# Robottino_V2.net
KiCad netlist of a schematic drawn in EAGLE
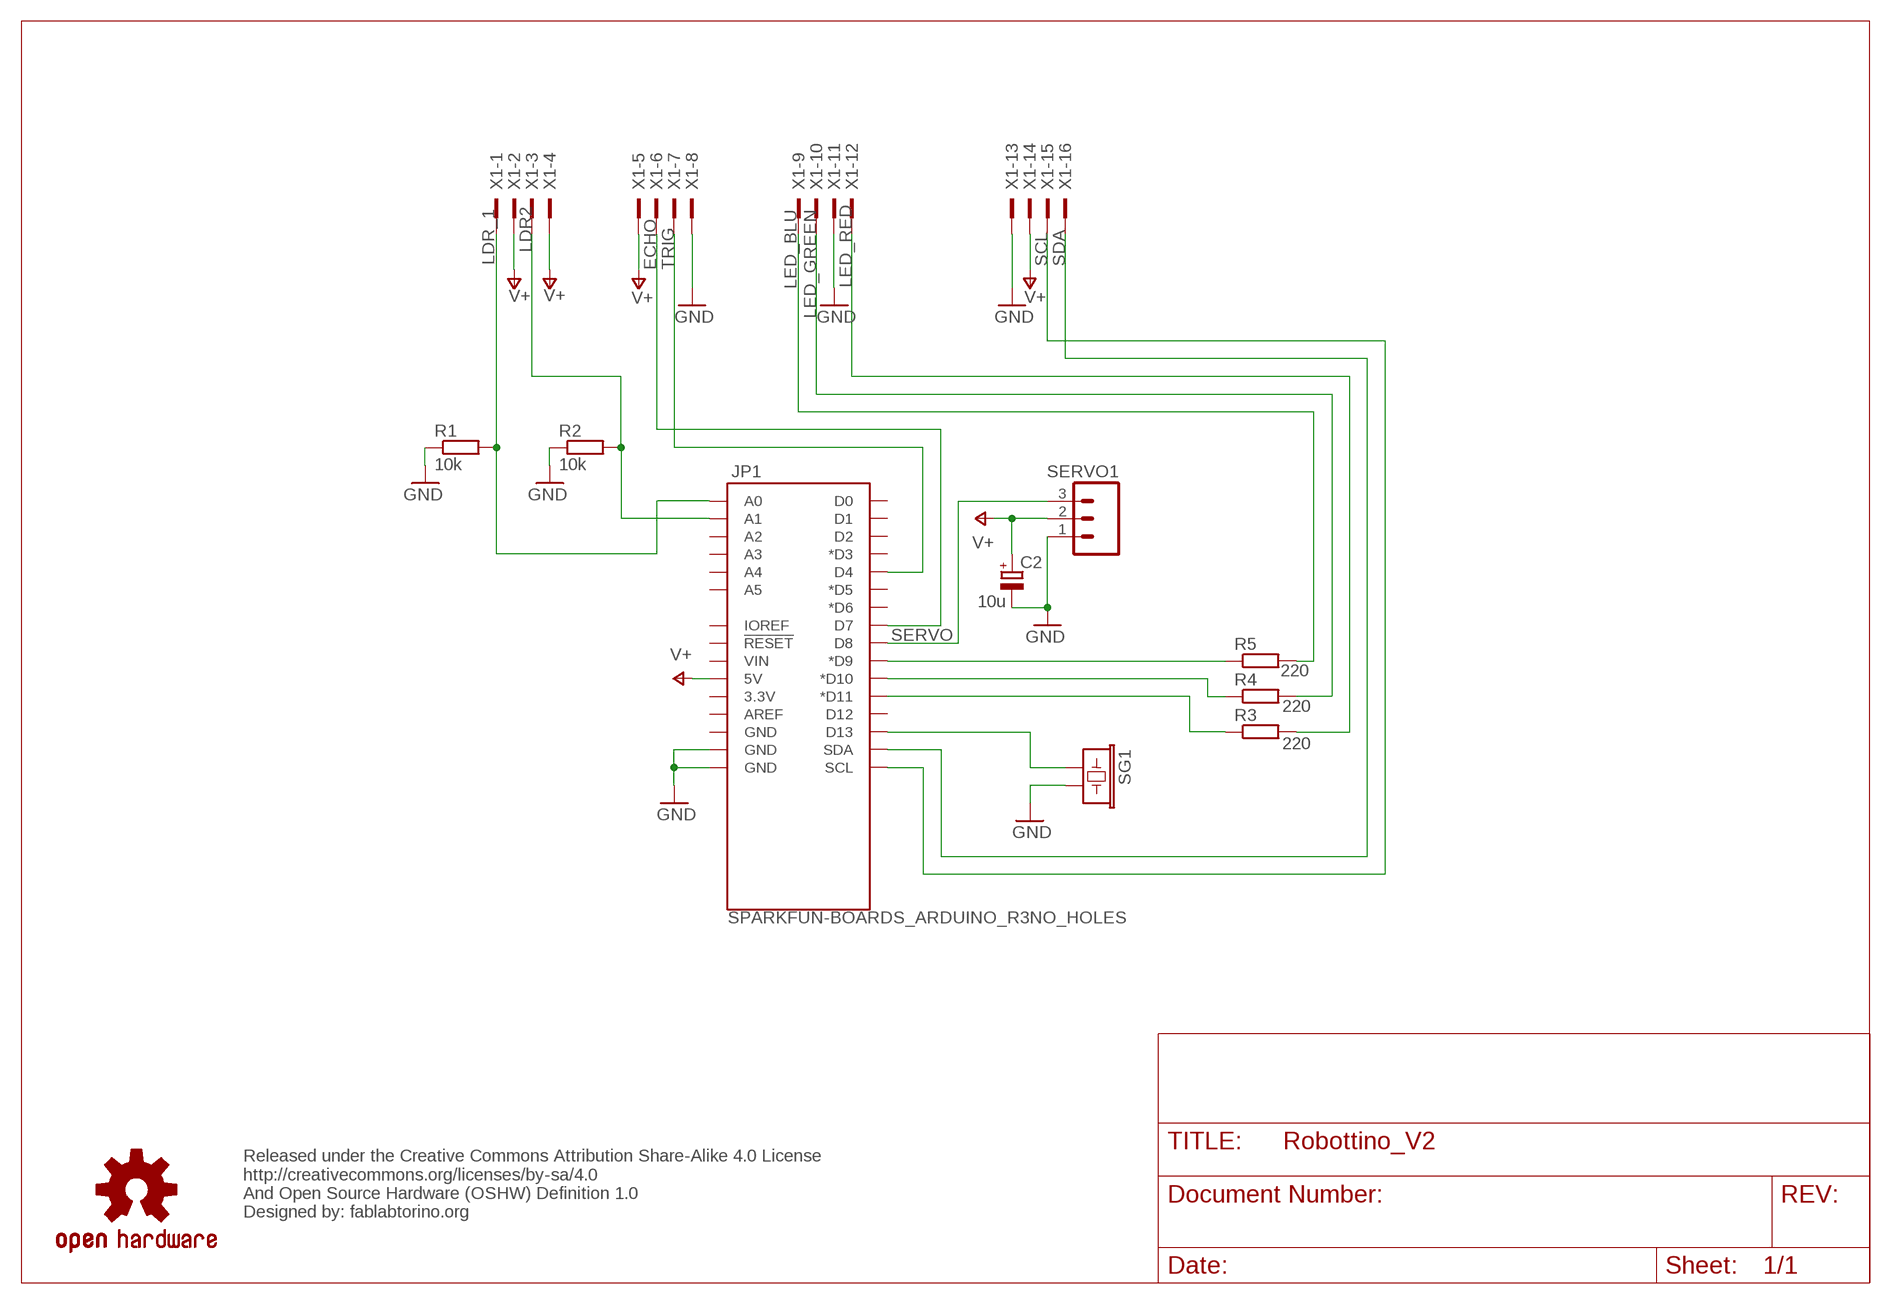
[diagram p0: schematic, sheet 1]

(export (version "E")
  (design (tool "Eeschema 10.0.6"))
  (components
    (comp (ref "C2")
      (value "10u")
      (footprint "eagle-import:E2,5-6")
      (libsource (lib "eagle-import") (part "CPOL-EUE2.5-6"))
    )
    (comp (ref "JP1")
      (value "SPARKFUN-BOARDS_ARDUINO_R3NO_HOLES")
      (footprint "eagle-import:SPARKFUN-BOARDS_ARDUINO_R3_NO_HOLES")
      (libsource (lib "eagle-import") (part "SPARKFUN-BOARDS_ARDUINO_R3NO_HOLES"))
    )
    (comp (ref "LOGO1")
      (value "OSHW-LOGOS")
      (footprint "eagle-import:OSHW-LOGO-S")
      (libsource (lib "eagle-import") (part "OSHW-LOGOS"))
    )
    (comp (ref "R1")
      (value "10k")
      (footprint "eagle-import:0309_10")
      (libsource (lib "eagle-import") (part "R-EU_0309/10"))
    )
    (comp (ref "R2")
      (value "10k")
      (footprint "eagle-import:0309_10")
      (libsource (lib "eagle-import") (part "R-EU_0309/10"))
    )
    (comp (ref "R3")
      (value "220")
      (footprint "eagle-import:0309_10")
      (libsource (lib "eagle-import") (part "R-EU_0309/10"))
    )
    (comp (ref "R4")
      (value "220")
      (footprint "eagle-import:0309_10")
      (libsource (lib "eagle-import") (part "R-EU_0309/10"))
    )
    (comp (ref "R5")
      (value "220")
      (footprint "eagle-import:0309_10")
      (libsource (lib "eagle-import") (part "R-EU_0309/10"))
    )
    (comp (ref "SERVO1")
      (value "M03POLAR")
      (footprint "eagle-import:MOLEX-1X3")
      (libsource (lib "eagle-import") (part "M03POLAR"))
    )
    (comp (ref "SG1")
      (value "SPARKFUN-ELECTROMECHANICAL_BUZZERPTH-NS-KIT")
      (footprint "eagle-import:SPARKFUN-ELECTROMECHANICAL_BUZZER-12MM-NS-KIT")
      (libsource (lib "eagle-import") (part "SPARKFUN-ELECTROMECHANICAL_BUZZERPTH-NS-KIT"))
    )
    (comp (ref "X1")
      (value "2516-")
      (footprint "eagle-import:PAK100_2500-16")
      (libsource (lib "eagle-import") (part "2516-"))
    )
  )
  (nets
    (net (code "1") (name "/ECHO") (class "Default")
      (node (ref "JP1") (pin "D4") (pinfunction "D4_D4") (pintype "bidirectional"))
      (node (ref "X1") (pin "7") (pinfunction "KL_7") (pintype "passive"))
    )
    (net (code "2") (name "/LDR2") (class "Default")
      (node (ref "JP1") (pin "A1") (pinfunction "A1_A1") (pintype "bidirectional"))
      (node (ref "R2") (pin "2") (pinfunction "2_2") (pintype "passive"))
      (node (ref "X1") (pin "3") (pinfunction "KL_3") (pintype "passive"))
    )
    (net (code "3") (name "/LDR_1") (class "Default")
      (node (ref "JP1") (pin "A0") (pinfunction "A0_A0") (pintype "bidirectional"))
      (node (ref "R1") (pin "2") (pinfunction "2_2") (pintype "passive"))
      (node (ref "X1") (pin "1") (pinfunction "KL_1") (pintype "passive"))
    )
    (net (code "4") (name "/LED_BLU") (class "Default")
      (node (ref "R5") (pin "2") (pinfunction "2_2") (pintype "passive"))
      (node (ref "X1") (pin "9") (pinfunction "KL_9") (pintype "passive"))
    )
    (net (code "5") (name "/LED_GREEN") (class "Default")
      (node (ref "R4") (pin "2") (pinfunction "2_2") (pintype "passive"))
      (node (ref "X1") (pin "10") (pinfunction "KL_10") (pintype "passive"))
    )
    (net (code "6") (name "/LED_RED") (class "Default")
      (node (ref "R3") (pin "2") (pinfunction "2_2") (pintype "passive"))
      (node (ref "X1") (pin "12") (pinfunction "KL_12") (pintype "passive"))
    )
    (net (code "7") (name "/SCL") (class "Default")
      (node (ref "JP1") (pin "SCL") (pinfunction "SCL_SCL") (pintype "bidirectional"))
      (node (ref "X1") (pin "15") (pinfunction "KL_15") (pintype "passive"))
    )
    (net (code "8") (name "/SDA") (class "Default")
      (node (ref "JP1") (pin "SDA") (pinfunction "SDA_SDA") (pintype "bidirectional"))
      (node (ref "X1") (pin "16") (pinfunction "KL_16") (pintype "passive"))
    )
    (net (code "9") (name "/SERVO") (class "Default")
      (node (ref "JP1") (pin "D8") (pinfunction "D8_D8") (pintype "bidirectional"))
      (node (ref "SERVO1") (pin "3") (pinfunction "3_3") (pintype "passive"))
    )
    (net (code "10") (name "/TRIG") (class "Default")
      (node (ref "JP1") (pin "D7") (pinfunction "D7_D7") (pintype "bidirectional"))
      (node (ref "X1") (pin "6") (pinfunction "KL_6") (pintype "passive"))
    )
    (net (code "11") (name "GND") (class "Default")
      (node (ref "C2") (pin "-") (pinfunction "-_-") (pintype "passive"))
      (node (ref "JP1") (pin "GND@1") (pinfunction "GND_GND@1") (pintype "bidirectional"))
      (node (ref "JP1") (pin "GND@2") (pinfunction "GND_GND@2") (pintype "bidirectional"))
      (node (ref "R1") (pin "1") (pinfunction "1_1") (pintype "passive"))
      (node (ref "R2") (pin "1") (pinfunction "1_1") (pintype "passive"))
      (node (ref "SERVO1") (pin "1") (pinfunction "1_1") (pintype "passive"))
      (node (ref "SG1") (pin "-") (pinfunction "2_-") (pintype "passive"))
      (node (ref "X1") (pin "11") (pinfunction "KL_11") (pintype "passive"))
      (node (ref "X1") (pin "13") (pinfunction "KL_13") (pintype "passive"))
      (node (ref "X1") (pin "8") (pinfunction "KL_8") (pintype "passive"))
    )
    (net (code "12") (name "Net-(JP1-*D9)") (class "Default")
      (node (ref "JP1") (pin "D9") (pinfunction "*D9_D9") (pintype "bidirectional"))
      (node (ref "R5") (pin "1") (pinfunction "1_1") (pintype "passive"))
    )
    (net (code "13") (name "Net-(JP1-*D10)") (class "Default")
      (node (ref "JP1") (pin "D10") (pinfunction "*D10_D10") (pintype "bidirectional"))
      (node (ref "R4") (pin "1") (pinfunction "1_1") (pintype "passive"))
    )
    (net (code "14") (name "Net-(JP1-*D11)") (class "Default")
      (node (ref "JP1") (pin "D11") (pinfunction "*D11_D11") (pintype "bidirectional"))
      (node (ref "R3") (pin "1") (pinfunction "1_1") (pintype "passive"))
    )
    (net (code "15") (name "Net-(SG1-1)") (class "Default")
      (node (ref "JP1") (pin "D13") (pinfunction "D13_D13") (pintype "bidirectional"))
      (node (ref "SG1") (pin "+") (pinfunction "1_+") (pintype "passive"))
    )
    (net (code "16") (name "V+") (class "Default")
      (node (ref "C2") (pin "+") (pinfunction "+_+") (pintype "passive"))
      (node (ref "JP1") (pin "5V") (pinfunction "5V_5V") (pintype "bidirectional"))
      (node (ref "SERVO1") (pin "2") (pinfunction "2_2") (pintype "passive"))
      (node (ref "X1") (pin "14") (pinfunction "KL_14") (pintype "passive"))
      (node (ref "X1") (pin "2") (pinfunction "KL_2") (pintype "passive"))
      (node (ref "X1") (pin "4") (pinfunction "KL_4") (pintype "passive"))
      (node (ref "X1") (pin "5") (pinfunction "KL_5") (pintype "passive"))
    )
    (net (code "17") (name "unconnected-(JP1-*D3-PadD3)") (class "Default")
      (node (ref "JP1") (pin "D3") (pinfunction "*D3_D3") (pintype "bidirectional"))
    )
    (net (code "18") (name "unconnected-(JP1-*D5-PadD5)") (class "Default")
      (node (ref "JP1") (pin "D5") (pinfunction "*D5_D5") (pintype "bidirectional"))
    )
    (net (code "19") (name "unconnected-(JP1-*D6-PadD6)") (class "Default")
      (node (ref "JP1") (pin "D6") (pinfunction "*D6_D6") (pintype "bidirectional"))
    )
    (net (code "20") (name "unconnected-(JP1-GND-PadGND@3)") (class "Default")
      (node (ref "JP1") (pin "GND@3") (pinfunction "GND_GND@3") (pintype "bidirectional"))
    )
    (net (code "21") (name "unconnected-(JP1-Pad3.3V)") (class "Default")
      (node (ref "JP1") (pin "3.3V") (pinfunction "3.3V_3.3V") (pintype "bidirectional"))
    )
    (net (code "22") (name "unconnected-(JP1-PadA2)") (class "Default")
      (node (ref "JP1") (pin "A2") (pinfunction "A2_A2") (pintype "bidirectional"))
    )
    (net (code "23") (name "unconnected-(JP1-PadA3)") (class "Default")
      (node (ref "JP1") (pin "A3") (pinfunction "A3_A3") (pintype "bidirectional"))
    )
    (net (code "24") (name "unconnected-(JP1-PadA4)") (class "Default")
      (node (ref "JP1") (pin "A4") (pinfunction "A4_A4") (pintype "bidirectional"))
    )
    (net (code "25") (name "unconnected-(JP1-PadA5)") (class "Default")
      (node (ref "JP1") (pin "A5") (pinfunction "A5_A5") (pintype "bidirectional"))
    )
    (net (code "26") (name "unconnected-(JP1-PadAREF)") (class "Default")
      (node (ref "JP1") (pin "AREF") (pinfunction "AREF_AREF") (pintype "bidirectional"))
    )
    (net (code "27") (name "unconnected-(JP1-PadD0)") (class "Default")
      (node (ref "JP1") (pin "D0") (pinfunction "D0_D0") (pintype "bidirectional"))
    )
    (net (code "28") (name "unconnected-(JP1-PadD1)") (class "Default")
      (node (ref "JP1") (pin "D1") (pinfunction "D1_D1") (pintype "bidirectional"))
    )
    (net (code "29") (name "unconnected-(JP1-PadD2)") (class "Default")
      (node (ref "JP1") (pin "D2") (pinfunction "D2_D2") (pintype "bidirectional"))
    )
    (net (code "30") (name "unconnected-(JP1-PadD12)") (class "Default")
      (node (ref "JP1") (pin "D12") (pinfunction "D12_D12") (pintype "bidirectional"))
    )
    (net (code "31") (name "unconnected-(JP1-PadIOREF)") (class "Default")
      (node (ref "JP1") (pin "IOREF") (pinfunction "IOREF_IOREF") (pintype "bidirectional"))
    )
    (net (code "32") (name "unconnected-(JP1-PadVIN)") (class "Default")
      (node (ref "JP1") (pin "VIN") (pinfunction "VIN_VIN") (pintype "bidirectional"))
    )
    (net (code "33") (name "unconnected-(JP1-~{RESET}-PadRESET@1)") (class "Default")
      (node (ref "JP1") (pin "RESET@1") (pinfunction "~{RESET}_RESET@1") (pintype "bidirectional"))
    )
  )
)
